# FAL65816_cpua.net
KiCad netlist of a schematic drawn in EAGLE
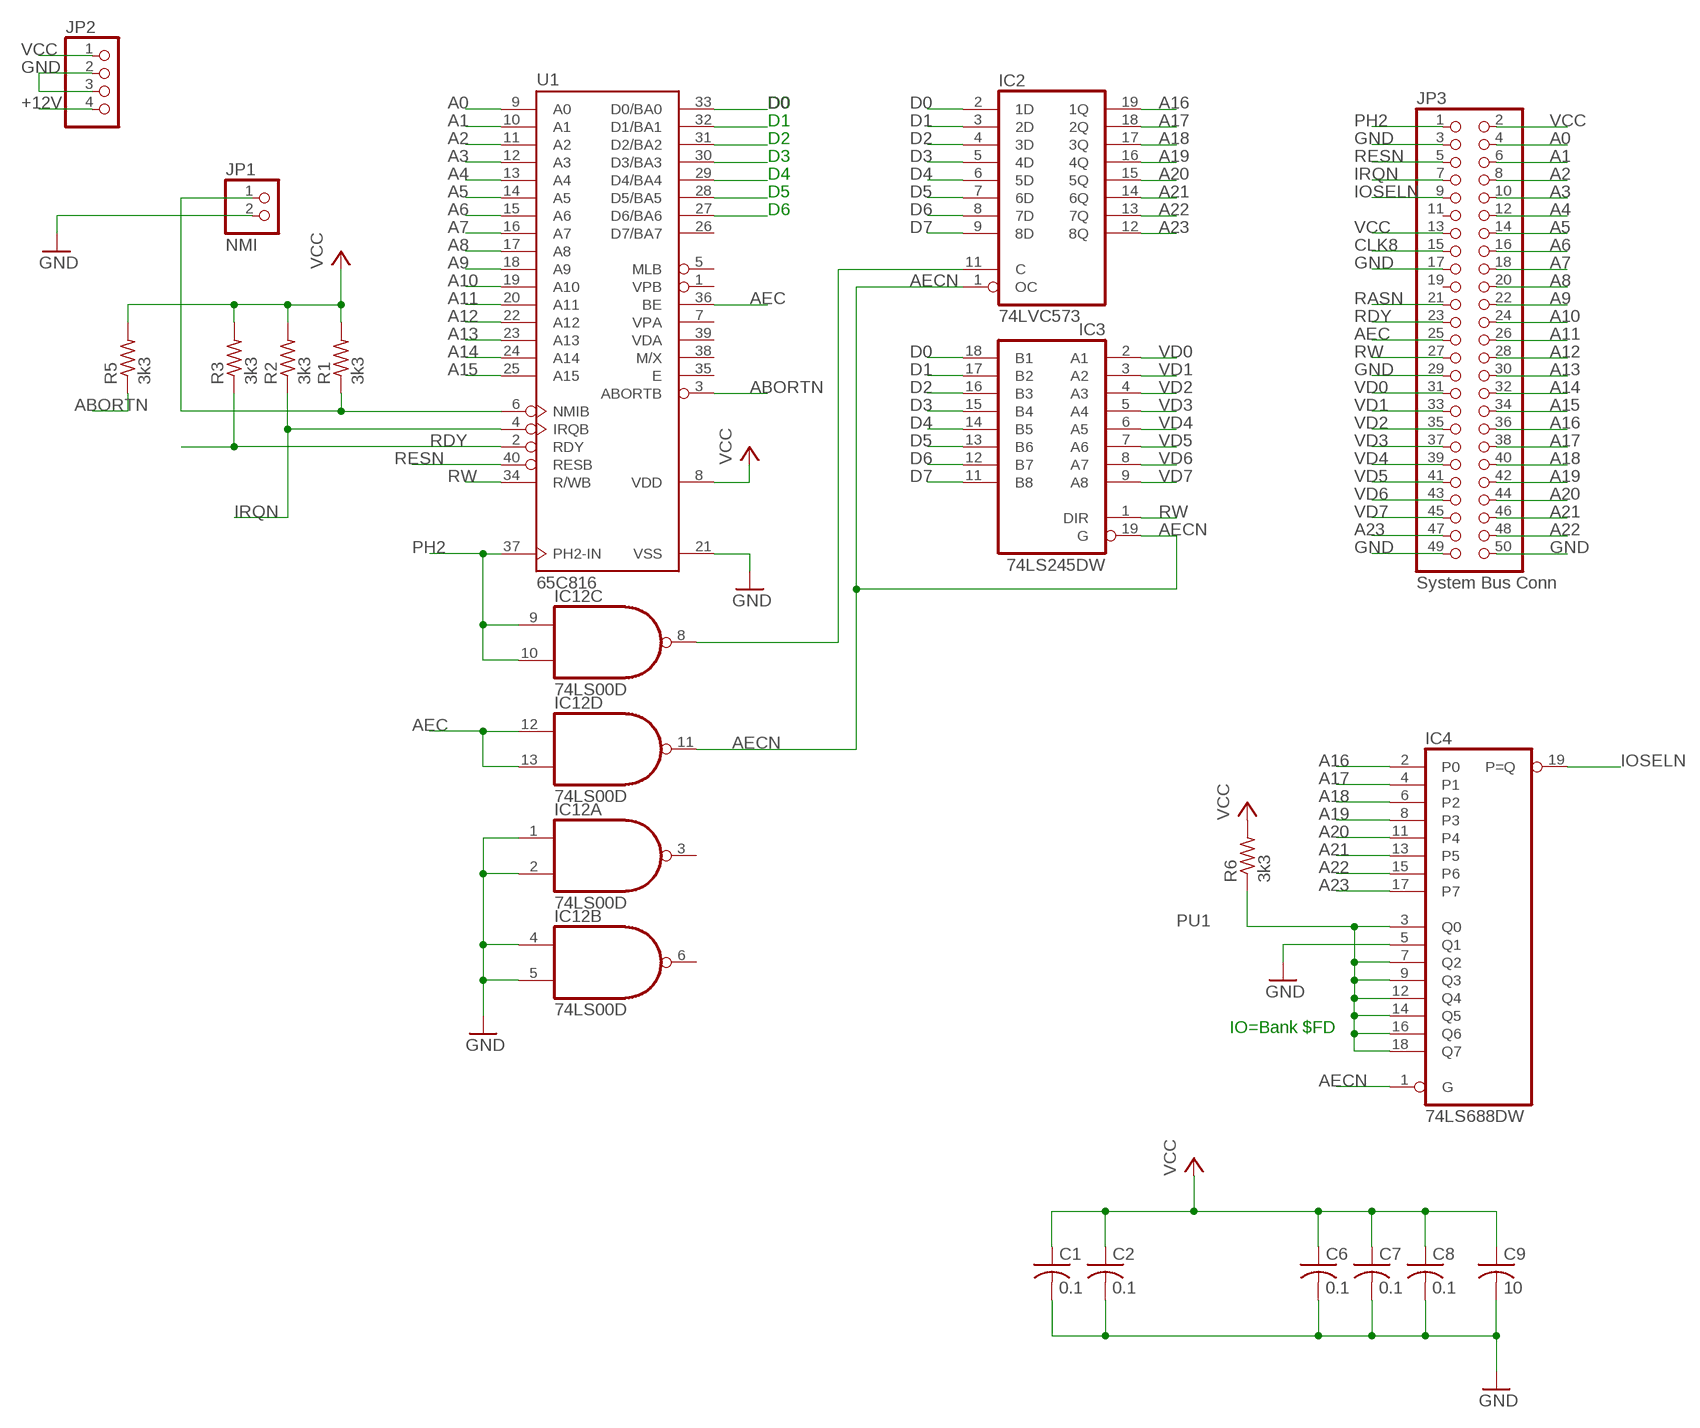
[diagram p0: schematic, sheet 1]

(export (version "E")
  (design (tool "Eeschema 10.0.6"))
  (components
    (comp (ref "C1")
      (value "0.1")
      (footprint "eagle-import:C050-024X044")
      (libsource (lib "eagle-import") (part "C-US050-024X044"))
    )
    (comp (ref "C2")
      (value "0.1")
      (footprint "eagle-import:C050-024X044")
      (libsource (lib "eagle-import") (part "C-US050-024X044"))
    )
    (comp (ref "C6")
      (value "0.1")
      (footprint "eagle-import:C050-024X044")
      (libsource (lib "eagle-import") (part "C-US050-024X044"))
    )
    (comp (ref "C7")
      (value "0.1")
      (footprint "eagle-import:C050-024X044")
      (libsource (lib "eagle-import") (part "C-US050-024X044"))
    )
    (comp (ref "C8")
      (value "0.1")
      (footprint "eagle-import:C050-024X044")
      (libsource (lib "eagle-import") (part "C-US050-024X044"))
    )
    (comp (ref "C9")
      (value "10")
      (footprint "eagle-import:C050-024X044")
      (libsource (lib "eagle-import") (part "C-US050-024X044"))
    )
    (comp (ref "IC2")
      (value "74LVC573")
      (footprint "eagle-import:SO20W")
      (libsource (lib "eagle-import") (part "74573LVC"))
    )
    (comp (ref "IC3")
      (value "74LS245DW")
      (footprint "eagle-import:SO20W")
      (libsource (lib "eagle-import") (part "74245DWLS"))
    )
    (comp (ref "IC4")
      (value "74LS688DW")
      (footprint "eagle-import:SO20W")
      (libsource (lib "eagle-import") (part "74688DWLS"))
    )
    (comp (ref "IC12")
      (value "74LS00D")
      (footprint "eagle-import:SO14")
      (libsource (lib "eagle-import") (part "7400DLS"))
    )
    (comp (ref "JP1")
      (value "NMI")
      (footprint "eagle-import:1X02")
      (libsource (lib "eagle-import") (part "PINHD-1X2"))
    )
    (comp (ref "JP2")
      (value "PINHD-1X4/90")
      (footprint "eagle-import:1X04_90")
      (libsource (lib "eagle-import") (part "PINHD-1X4/90"))
    )
    (comp (ref "JP3")
      (value "System Bus Conn")
      (footprint "eagle-import:2X25_90")
      (libsource (lib "eagle-import") (part "PINHD-2X25/90"))
    )
    (comp (ref "R1")
      (value "3k3")
      (footprint "eagle-import:0207_10")
      (libsource (lib "eagle-import") (part "R-US_0207/10"))
    )
    (comp (ref "R2")
      (value "3k3")
      (footprint "eagle-import:0207_10")
      (libsource (lib "eagle-import") (part "R-US_0207/10"))
    )
    (comp (ref "R3")
      (value "3k3")
      (footprint "eagle-import:0207_10")
      (libsource (lib "eagle-import") (part "R-US_0207/10"))
    )
    (comp (ref "R5")
      (value "3k3")
      (footprint "eagle-import:0207_10")
      (libsource (lib "eagle-import") (part "R-US_0207/10"))
    )
    (comp (ref "R6")
      (value "3k3")
      (footprint "eagle-import:0204_7")
      (libsource (lib "eagle-import") (part "R-US_0204/7"))
    )
    (comp (ref "U1")
      (value "65C816")
      (footprint "eagle-import:DIP-40")
      (libsource (lib "eagle-import") (part "W65C816SP"))
    )
  )
  (nets
    (net (code "1") (name "/+12V") (class "Default")
      (node (ref "JP2") (pin "4") (pinfunction "4_4") (pintype "passive"))
    )
    (net (code "2") (name "/A0") (class "Default")
      (node (ref "JP3") (pin "4") (pinfunction "4_4") (pintype "passive"))
      (node (ref "U1") (pin "9") (pinfunction "A0_9") (pintype "bidirectional"))
    )
    (net (code "3") (name "/A1") (class "Default")
      (node (ref "JP3") (pin "6") (pinfunction "6_6") (pintype "passive"))
      (node (ref "U1") (pin "10") (pinfunction "A1_10") (pintype "bidirectional"))
    )
    (net (code "4") (name "/A2") (class "Default")
      (node (ref "JP3") (pin "8") (pinfunction "8_8") (pintype "passive"))
      (node (ref "U1") (pin "11") (pinfunction "A2_11") (pintype "bidirectional"))
    )
    (net (code "5") (name "/A3") (class "Default")
      (node (ref "JP3") (pin "10") (pinfunction "10_10") (pintype "passive"))
      (node (ref "U1") (pin "12") (pinfunction "A3_12") (pintype "bidirectional"))
    )
    (net (code "6") (name "/A4") (class "Default")
      (node (ref "JP3") (pin "12") (pinfunction "12_12") (pintype "passive"))
      (node (ref "U1") (pin "13") (pinfunction "A4_13") (pintype "bidirectional"))
    )
    (net (code "7") (name "/A5") (class "Default")
      (node (ref "JP3") (pin "14") (pinfunction "14_14") (pintype "passive"))
      (node (ref "U1") (pin "14") (pinfunction "A5_14") (pintype "bidirectional"))
    )
    (net (code "8") (name "/A6") (class "Default")
      (node (ref "JP3") (pin "16") (pinfunction "16_16") (pintype "passive"))
      (node (ref "U1") (pin "15") (pinfunction "A6_15") (pintype "bidirectional"))
    )
    (net (code "9") (name "/A7") (class "Default")
      (node (ref "JP3") (pin "18") (pinfunction "18_18") (pintype "passive"))
      (node (ref "U1") (pin "16") (pinfunction "A7_16") (pintype "bidirectional"))
    )
    (net (code "10") (name "/A8") (class "Default")
      (node (ref "JP3") (pin "20") (pinfunction "20_20") (pintype "passive"))
      (node (ref "U1") (pin "17") (pinfunction "A8_17") (pintype "bidirectional"))
    )
    (net (code "11") (name "/A9") (class "Default")
      (node (ref "JP3") (pin "22") (pinfunction "22_22") (pintype "passive"))
      (node (ref "U1") (pin "18") (pinfunction "A9_18") (pintype "bidirectional"))
    )
    (net (code "12") (name "/A10") (class "Default")
      (node (ref "JP3") (pin "24") (pinfunction "24_24") (pintype "passive"))
      (node (ref "U1") (pin "19") (pinfunction "A10_19") (pintype "bidirectional"))
    )
    (net (code "13") (name "/A11") (class "Default")
      (node (ref "JP3") (pin "26") (pinfunction "26_26") (pintype "passive"))
      (node (ref "U1") (pin "20") (pinfunction "A11_20") (pintype "bidirectional"))
    )
    (net (code "14") (name "/A12") (class "Default")
      (node (ref "JP3") (pin "28") (pinfunction "28_28") (pintype "passive"))
      (node (ref "U1") (pin "22") (pinfunction "A12_22") (pintype "bidirectional"))
    )
    (net (code "15") (name "/A13") (class "Default")
      (node (ref "JP3") (pin "30") (pinfunction "30_30") (pintype "passive"))
      (node (ref "U1") (pin "23") (pinfunction "A13_23") (pintype "bidirectional"))
    )
    (net (code "16") (name "/A14") (class "Default")
      (node (ref "JP3") (pin "32") (pinfunction "32_32") (pintype "passive"))
      (node (ref "U1") (pin "24") (pinfunction "A14_24") (pintype "bidirectional"))
    )
    (net (code "17") (name "/A15") (class "Default")
      (node (ref "JP3") (pin "34") (pinfunction "34_34") (pintype "passive"))
      (node (ref "U1") (pin "25") (pinfunction "A15_25") (pintype "bidirectional"))
    )
    (net (code "18") (name "/A16") (class "Default")
      (node (ref "IC2") (pin "19") (pinfunction "1Q_19") (pintype "tri_state"))
      (node (ref "IC4") (pin "2") (pinfunction "P0_2") (pintype "input"))
      (node (ref "JP3") (pin "36") (pinfunction "36_36") (pintype "passive"))
    )
    (net (code "19") (name "/A17") (class "Default")
      (node (ref "IC2") (pin "18") (pinfunction "2Q_18") (pintype "tri_state"))
      (node (ref "IC4") (pin "4") (pinfunction "P1_4") (pintype "input"))
      (node (ref "JP3") (pin "38") (pinfunction "38_38") (pintype "passive"))
    )
    (net (code "20") (name "/A18") (class "Default")
      (node (ref "IC2") (pin "17") (pinfunction "3Q_17") (pintype "tri_state"))
      (node (ref "IC4") (pin "6") (pinfunction "P2_6") (pintype "input"))
      (node (ref "JP3") (pin "40") (pinfunction "40_40") (pintype "passive"))
    )
    (net (code "21") (name "/A19") (class "Default")
      (node (ref "IC2") (pin "16") (pinfunction "4Q_16") (pintype "tri_state"))
      (node (ref "IC4") (pin "8") (pinfunction "P3_8") (pintype "input"))
      (node (ref "JP3") (pin "42") (pinfunction "42_42") (pintype "passive"))
    )
    (net (code "22") (name "/A20") (class "Default")
      (node (ref "IC2") (pin "15") (pinfunction "5Q_15") (pintype "tri_state"))
      (node (ref "IC4") (pin "11") (pinfunction "P4_11") (pintype "input"))
      (node (ref "JP3") (pin "44") (pinfunction "44_44") (pintype "passive"))
    )
    (net (code "23") (name "/A21") (class "Default")
      (node (ref "IC2") (pin "14") (pinfunction "6Q_14") (pintype "tri_state"))
      (node (ref "IC4") (pin "13") (pinfunction "P5_13") (pintype "input"))
      (node (ref "JP3") (pin "46") (pinfunction "46_46") (pintype "passive"))
    )
    (net (code "24") (name "/A22") (class "Default")
      (node (ref "IC2") (pin "13") (pinfunction "7Q_13") (pintype "tri_state"))
      (node (ref "IC4") (pin "15") (pinfunction "P6_15") (pintype "input"))
      (node (ref "JP3") (pin "48") (pinfunction "48_48") (pintype "passive"))
    )
    (net (code "25") (name "/A23") (class "Default")
      (node (ref "IC2") (pin "12") (pinfunction "8Q_12") (pintype "tri_state"))
      (node (ref "IC4") (pin "17") (pinfunction "P7_17") (pintype "input"))
      (node (ref "JP3") (pin "47") (pinfunction "47_47") (pintype "passive"))
    )
    (net (code "26") (name "/ABORTN") (class "Default")
      (node (ref "R5") (pin "1") (pinfunction "1_1") (pintype "passive"))
      (node (ref "U1") (pin "3") (pinfunction "ABORTB_3") (pintype "input"))
    )
    (net (code "27") (name "/AEC") (class "Default")
      (node (ref "IC12") (pin "12") (pinfunction "I0_12") (pintype "input"))
      (node (ref "IC12") (pin "13") (pinfunction "I1_13") (pintype "input"))
      (node (ref "JP3") (pin "25") (pinfunction "25_25") (pintype "passive"))
      (node (ref "U1") (pin "36") (pinfunction "BE_36") (pintype "input"))
    )
    (net (code "28") (name "/AECN") (class "Default")
      (node (ref "IC12") (pin "11") (pinfunction "O_11") (pintype "output"))
      (node (ref "IC2") (pin "1") (pinfunction "OC_1") (pintype "input"))
      (node (ref "IC3") (pin "19") (pinfunction "G_19") (pintype "input"))
      (node (ref "IC4") (pin "1") (pinfunction "G_1") (pintype "input"))
    )
    (net (code "29") (name "/CLK8") (class "Default")
      (node (ref "JP3") (pin "15") (pinfunction "15_15") (pintype "passive"))
    )
    (net (code "30") (name "/D0") (class "Default")
      (node (ref "IC2") (pin "2") (pinfunction "1D_2") (pintype "input"))
      (node (ref "IC3") (pin "18") (pinfunction "B1_18") (pintype "bidirectional"))
      (node (ref "U1") (pin "33") (pinfunction "D0/BA0_33") (pintype "bidirectional"))
    )
    (net (code "31") (name "/D1") (class "Default")
      (node (ref "IC2") (pin "3") (pinfunction "2D_3") (pintype "input"))
      (node (ref "IC3") (pin "17") (pinfunction "B2_17") (pintype "bidirectional"))
      (node (ref "U1") (pin "32") (pinfunction "D1/BA1_32") (pintype "bidirectional"))
    )
    (net (code "32") (name "/D2") (class "Default")
      (node (ref "IC2") (pin "4") (pinfunction "3D_4") (pintype "input"))
      (node (ref "IC3") (pin "16") (pinfunction "B3_16") (pintype "bidirectional"))
      (node (ref "U1") (pin "31") (pinfunction "D2/BA2_31") (pintype "bidirectional"))
    )
    (net (code "33") (name "/D3") (class "Default")
      (node (ref "IC2") (pin "5") (pinfunction "4D_5") (pintype "input"))
      (node (ref "IC3") (pin "15") (pinfunction "B4_15") (pintype "bidirectional"))
      (node (ref "U1") (pin "30") (pinfunction "D3/BA3_30") (pintype "bidirectional"))
    )
    (net (code "34") (name "/D4") (class "Default")
      (node (ref "IC2") (pin "6") (pinfunction "5D_6") (pintype "input"))
      (node (ref "IC3") (pin "14") (pinfunction "B5_14") (pintype "bidirectional"))
      (node (ref "U1") (pin "29") (pinfunction "D4/BA4_29") (pintype "bidirectional"))
    )
    (net (code "35") (name "/D5") (class "Default")
      (node (ref "IC2") (pin "7") (pinfunction "6D_7") (pintype "input"))
      (node (ref "IC3") (pin "13") (pinfunction "B6_13") (pintype "bidirectional"))
      (node (ref "U1") (pin "28") (pinfunction "D5/BA5_28") (pintype "bidirectional"))
    )
    (net (code "36") (name "/D6") (class "Default")
      (node (ref "IC2") (pin "8") (pinfunction "7D_8") (pintype "input"))
      (node (ref "IC3") (pin "12") (pinfunction "B7_12") (pintype "bidirectional"))
      (node (ref "U1") (pin "27") (pinfunction "D6/BA6_27") (pintype "bidirectional"))
    )
    (net (code "37") (name "/D7") (class "Default")
      (node (ref "IC2") (pin "9") (pinfunction "8D_9") (pintype "input"))
      (node (ref "IC3") (pin "11") (pinfunction "B8_11") (pintype "bidirectional"))
    )
    (net (code "38") (name "/IOSELN") (class "Default")
      (node (ref "IC4") (pin "19") (pinfunction "P=Q_19") (pintype "output"))
      (node (ref "JP3") (pin "9") (pinfunction "9_9") (pintype "passive"))
    )
    (net (code "39") (name "/IRQN") (class "Default")
      (node (ref "JP3") (pin "7") (pinfunction "7_7") (pintype "passive"))
      (node (ref "R2") (pin "1") (pinfunction "1_1") (pintype "passive"))
      (node (ref "U1") (pin "4") (pinfunction "IRQB_4") (pintype "input"))
    )
    (net (code "40") (name "/PH2") (class "Default")
      (node (ref "IC12") (pin "10") (pinfunction "I1_10") (pintype "input"))
      (node (ref "IC12") (pin "9") (pinfunction "I0_9") (pintype "input"))
      (node (ref "JP3") (pin "1") (pinfunction "1_1") (pintype "passive"))
      (node (ref "U1") (pin "37") (pinfunction "PH2-IN_37") (pintype "input"))
    )
    (net (code "41") (name "/PU1") (class "Default")
      (node (ref "IC4") (pin "12") (pinfunction "Q4_12") (pintype "input"))
      (node (ref "IC4") (pin "14") (pinfunction "Q5_14") (pintype "input"))
      (node (ref "IC4") (pin "16") (pinfunction "Q6_16") (pintype "input"))
      (node (ref "IC4") (pin "18") (pinfunction "Q7_18") (pintype "input"))
      (node (ref "IC4") (pin "3") (pinfunction "Q0_3") (pintype "input"))
      (node (ref "IC4") (pin "7") (pinfunction "Q2_7") (pintype "input"))
      (node (ref "IC4") (pin "9") (pinfunction "Q3_9") (pintype "input"))
      (node (ref "R6") (pin "1") (pinfunction "1_1") (pintype "passive"))
    )
    (net (code "42") (name "/RASN") (class "Default")
      (node (ref "JP3") (pin "21") (pinfunction "21_21") (pintype "passive"))
    )
    (net (code "43") (name "/RDY") (class "Default")
      (node (ref "JP3") (pin "23") (pinfunction "23_23") (pintype "passive"))
      (node (ref "R3") (pin "1") (pinfunction "1_1") (pintype "passive"))
      (node (ref "U1") (pin "2") (pinfunction "RDY_2") (pintype "bidirectional"))
    )
    (net (code "44") (name "/RESN") (class "Default")
      (node (ref "JP3") (pin "5") (pinfunction "5_5") (pintype "passive"))
      (node (ref "U1") (pin "40") (pinfunction "RESB_40") (pintype "input"))
    )
    (net (code "45") (name "/RW") (class "Default")
      (node (ref "IC3") (pin "1") (pinfunction "DIR_1") (pintype "input"))
      (node (ref "JP3") (pin "27") (pinfunction "27_27") (pintype "passive"))
      (node (ref "U1") (pin "34") (pinfunction "R/WB_34") (pintype "output"))
    )
    (net (code "46") (name "/VD0") (class "Default")
      (node (ref "IC3") (pin "2") (pinfunction "A1_2") (pintype "bidirectional"))
      (node (ref "JP3") (pin "31") (pinfunction "31_31") (pintype "passive"))
    )
    (net (code "47") (name "/VD1") (class "Default")
      (node (ref "IC3") (pin "3") (pinfunction "A2_3") (pintype "bidirectional"))
      (node (ref "JP3") (pin "33") (pinfunction "33_33") (pintype "passive"))
    )
    (net (code "48") (name "/VD2") (class "Default")
      (node (ref "IC3") (pin "4") (pinfunction "A3_4") (pintype "bidirectional"))
      (node (ref "JP3") (pin "35") (pinfunction "35_35") (pintype "passive"))
    )
    (net (code "49") (name "/VD3") (class "Default")
      (node (ref "IC3") (pin "5") (pinfunction "A4_5") (pintype "bidirectional"))
      (node (ref "JP3") (pin "37") (pinfunction "37_37") (pintype "passive"))
    )
    (net (code "50") (name "/VD4") (class "Default")
      (node (ref "IC3") (pin "6") (pinfunction "A5_6") (pintype "bidirectional"))
      (node (ref "JP3") (pin "39") (pinfunction "39_39") (pintype "passive"))
    )
    (net (code "51") (name "/VD5") (class "Default")
      (node (ref "IC3") (pin "7") (pinfunction "A6_7") (pintype "bidirectional"))
      (node (ref "JP3") (pin "41") (pinfunction "41_41") (pintype "passive"))
    )
    (net (code "52") (name "/VD6") (class "Default")
      (node (ref "IC3") (pin "8") (pinfunction "A7_8") (pintype "bidirectional"))
      (node (ref "JP3") (pin "43") (pinfunction "43_43") (pintype "passive"))
    )
    (net (code "53") (name "/VD7") (class "Default")
      (node (ref "IC3") (pin "9") (pinfunction "A8_9") (pintype "bidirectional"))
      (node (ref "JP3") (pin "45") (pinfunction "45_45") (pintype "passive"))
    )
    (net (code "54") (name "GND") (class "Default")
      (node (ref "C1") (pin "2") (pinfunction "2_2") (pintype "passive"))
      (node (ref "C2") (pin "2") (pinfunction "2_2") (pintype "passive"))
      (node (ref "C6") (pin "2") (pinfunction "2_2") (pintype "passive"))
      (node (ref "C7") (pin "2") (pinfunction "2_2") (pintype "passive"))
      (node (ref "C8") (pin "2") (pinfunction "2_2") (pintype "passive"))
      (node (ref "C9") (pin "2") (pinfunction "2_2") (pintype "passive"))
      (node (ref "IC12") (pin "1") (pinfunction "I0_1") (pintype "input"))
      (node (ref "IC12") (pin "2") (pinfunction "I1_2") (pintype "input"))
      (node (ref "IC12") (pin "4") (pinfunction "I0_4") (pintype "input"))
      (node (ref "IC12") (pin "5") (pinfunction "I1_5") (pintype "input"))
      (node (ref "IC4") (pin "5") (pinfunction "Q1_5") (pintype "input"))
      (node (ref "JP1") (pin "2") (pinfunction "2_2") (pintype "passive"))
      (node (ref "JP2") (pin "2") (pinfunction "2_2") (pintype "passive"))
      (node (ref "JP2") (pin "3") (pinfunction "3_3") (pintype "passive"))
      (node (ref "JP3") (pin "17") (pinfunction "17_17") (pintype "passive"))
      (node (ref "JP3") (pin "29") (pinfunction "29_29") (pintype "passive"))
      (node (ref "JP3") (pin "3") (pinfunction "3_3") (pintype "passive"))
      (node (ref "JP3") (pin "49") (pinfunction "49_49") (pintype "passive"))
      (node (ref "JP3") (pin "50") (pinfunction "50_50") (pintype "passive"))
      (node (ref "U1") (pin "21") (pinfunction "VSS_21") (pintype "power_in"))
    )
    (net (code "55") (name "Net-(IC12C-O)") (class "Default")
      (node (ref "IC12") (pin "8") (pinfunction "O_8") (pintype "output"))
      (node (ref "IC2") (pin "11") (pinfunction "C_11") (pintype "input"))
    )
    (net (code "56") (name "Net-(U1-NMIB)") (class "Default")
      (node (ref "JP1") (pin "1") (pinfunction "1_1") (pintype "passive"))
      (node (ref "R1") (pin "1") (pinfunction "1_1") (pintype "passive"))
      (node (ref "U1") (pin "6") (pinfunction "NMIB_6") (pintype "input"))
    )
    (net (code "57") (name "VCC") (class "Default")
      (node (ref "C1") (pin "1") (pinfunction "1_1") (pintype "passive"))
      (node (ref "C2") (pin "1") (pinfunction "1_1") (pintype "passive"))
      (node (ref "C6") (pin "1") (pinfunction "1_1") (pintype "passive"))
      (node (ref "C7") (pin "1") (pinfunction "1_1") (pintype "passive"))
      (node (ref "C8") (pin "1") (pinfunction "1_1") (pintype "passive"))
      (node (ref "C9") (pin "1") (pinfunction "1_1") (pintype "passive"))
      (node (ref "JP2") (pin "1") (pinfunction "1_1") (pintype "passive"))
      (node (ref "JP3") (pin "13") (pinfunction "13_13") (pintype "passive"))
      (node (ref "JP3") (pin "2") (pinfunction "2_2") (pintype "passive"))
      (node (ref "R1") (pin "2") (pinfunction "2_2") (pintype "passive"))
      (node (ref "R2") (pin "2") (pinfunction "2_2") (pintype "passive"))
      (node (ref "R3") (pin "2") (pinfunction "2_2") (pintype "passive"))
      (node (ref "R5") (pin "2") (pinfunction "2_2") (pintype "passive"))
      (node (ref "R6") (pin "2") (pinfunction "2_2") (pintype "passive"))
      (node (ref "U1") (pin "8") (pinfunction "VDD_8") (pintype "power_in"))
    )
    (net (code "58") (name "unconnected-(IC12A-O-Pad3)") (class "Default")
      (node (ref "IC12") (pin "3") (pinfunction "O_3") (pintype "output"))
    )
    (net (code "59") (name "unconnected-(IC12B-O-Pad6)") (class "Default")
      (node (ref "IC12") (pin "6") (pinfunction "O_6") (pintype "output"))
    )
    (net (code "60") (name "unconnected-(JP3-Pad11)") (class "Default")
      (node (ref "JP3") (pin "11") (pinfunction "11_11") (pintype "passive"))
    )
    (net (code "61") (name "unconnected-(JP3-Pad19)") (class "Default")
      (node (ref "JP3") (pin "19") (pinfunction "19_19") (pintype "passive"))
    )
    (net (code "62") (name "unconnected-(U1-D7{slash}BA7-Pad26)") (class "Default")
      (node (ref "U1") (pin "26") (pinfunction "D7/BA7_26") (pintype "bidirectional"))
    )
    (net (code "63") (name "unconnected-(U1-E-Pad35)") (class "Default")
      (node (ref "U1") (pin "35") (pinfunction "E_35") (pintype "output"))
    )
    (net (code "64") (name "unconnected-(U1-MLB-Pad5)") (class "Default")
      (node (ref "U1") (pin "5") (pinfunction "MLB_5") (pintype "output"))
    )
    (net (code "65") (name "unconnected-(U1-M{slash}X-Pad38)") (class "Default")
      (node (ref "U1") (pin "38") (pinfunction "M/X_38") (pintype "output"))
    )
    (net (code "66") (name "unconnected-(U1-VDA-Pad39)") (class "Default")
      (node (ref "U1") (pin "39") (pinfunction "VDA_39") (pintype "output"))
    )
    (net (code "67") (name "unconnected-(U1-VPA-Pad7)") (class "Default")
      (node (ref "U1") (pin "7") (pinfunction "VPA_7") (pintype "output"))
    )
    (net (code "68") (name "unconnected-(U1-VPB-Pad1)") (class "Default")
      (node (ref "U1") (pin "1") (pinfunction "VPB_1") (pintype "output"))
    )
  )
)
